# 780-00001_rev2_Pg3_SCH_Sinistro_ASP.net
KiCad netlist of a schematic drawn in Altium Designer
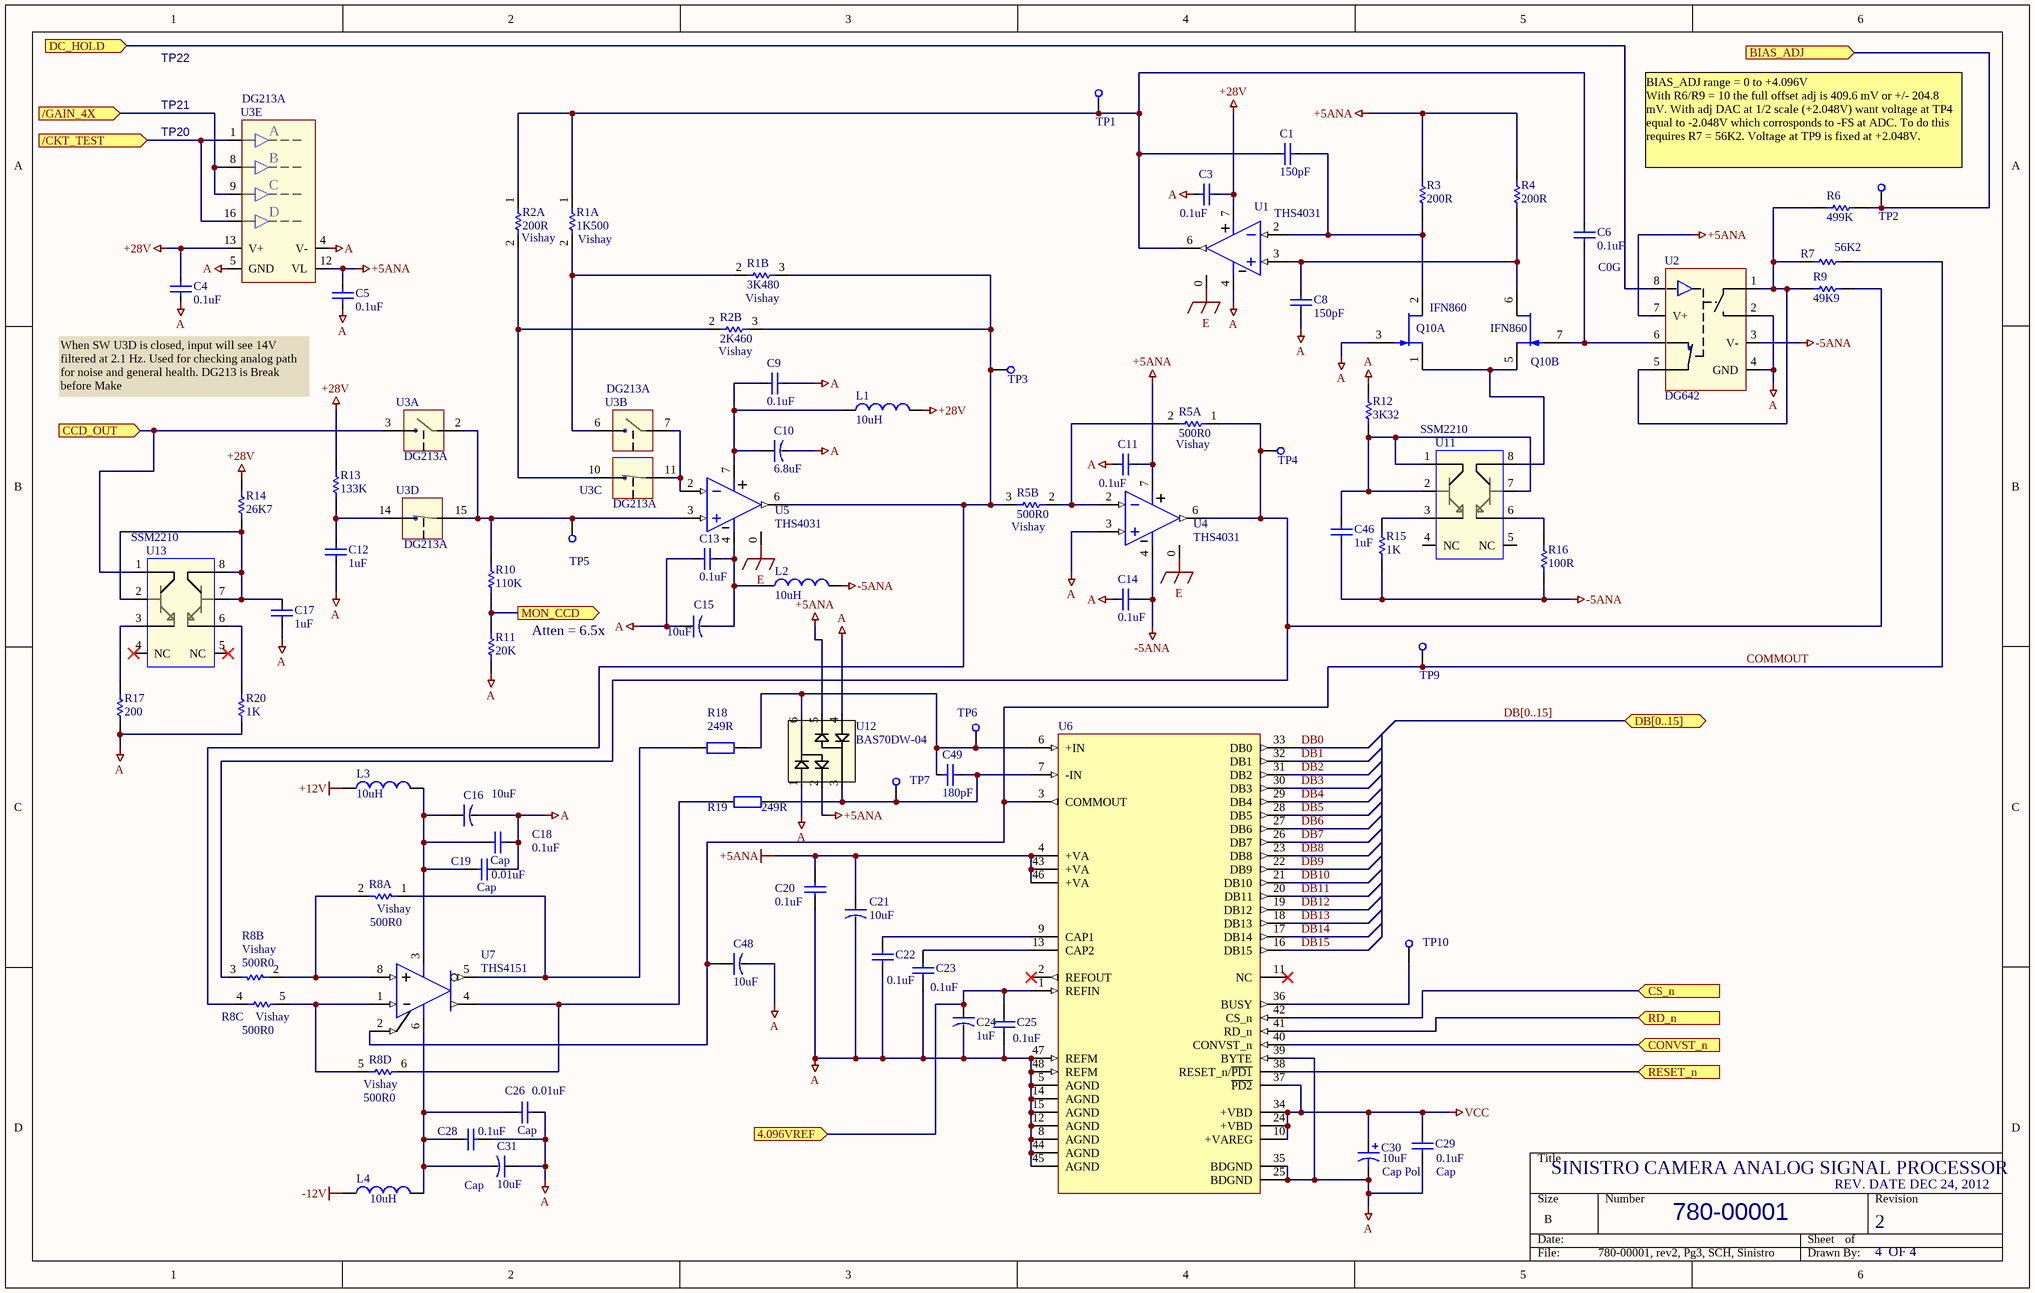
[diagram p0: 780-00001, rev2, Pg3, SCH, Sinistro ASP.SchDoc]

(export (version "E")
  (design (tool "Eeschema 10.0.6"))
  (components
    (comp (ref "C1")
      (value "150pF")
      (footprint "SMD_0805")
      (description "Capacitor")
      (fields (field (name "MANUFACTURER") "AVX") (field (name "Comment") "Cap SMD"))
      (libsource (lib "Richs Schematic Components") (part "Cap SMD"))
    )
    (comp (ref "C3")
      (value "0.1uF")
      (footprint "SMD_0805")
      (description "Capacitor")
      (fields (field (name "MANUFACTURER") "AVX") (field (name "Comment") "Cap"))
      (libsource (lib "Richs Schematic Components") (part "Cap SMD"))
    )
    (comp (ref "C4")
      (value "0.1uF")
      (footprint "SMD_0805")
      (description "Capacitor")
      (fields (field (name "MANUFACTURER") "AVX") (field (name "Comment") "Cap"))
      (libsource (lib "Richs Schematic Components") (part "Cap SMD"))
    )
    (comp (ref "C5")
      (value "0.1uF")
      (footprint "SMD_0805")
      (description "Capacitor")
      (fields (field (name "MANUFACTURER") "AVX") (field (name "Comment") "Cap"))
      (libsource (lib "Richs Schematic Components") (part "Cap SMD"))
    )
    (comp (ref "C6")
      (value "C0G")
      (footprint "1812")
      (description "Capacitor")
      (fields (field (name "ALTIUM_VALUE") "0.1uF") (field (name "MANUFACTURER") "TDK"))
      (libsource (lib "Richs Schematic Components") (part "Cap SMD"))
    )
    (comp (ref "C8")
      (value "150pF")
      (footprint "SMD_0805")
      (description "Capacitor")
      (fields (field (name "MANUFACTURER") "AVX") (field (name "Comment") "Cap SMD"))
      (libsource (lib "Richs Schematic Components") (part "Cap SMD"))
    )
    (comp (ref "C9")
      (value "0.1uF")
      (footprint "SMD_0805")
      (description "Capacitor")
      (fields (field (name "MANUFACTURER") "AVX") (field (name "Comment") "Cap"))
      (libsource (lib "Richs Schematic Components") (part "Cap SMD"))
    )
    (comp (ref "C10")
      (value "6.8uF")
      (footprint "SMD_CAP_6032")
      (description "outline 6.0mm x 3.2mm")
      (fields (field (name "MANUFACTURER") "Nichicon") (field (name "Comment") "35V"))
      (libsource (lib "Richs Schematic Components") (part "Cap Tant 35V"))
    )
    (comp (ref "C11")
      (value "0.1uF")
      (footprint "SMD_0805")
      (description "Capacitor")
      (fields (field (name "MANUFACTURER") "AVX") (field (name "Comment") "Cap"))
      (libsource (lib "Richs Schematic Components") (part "Cap SMD"))
    )
    (comp (ref "C12")
      (value "1uF")
      (footprint "SMD_0805")
      (description "Capacitor")
      (fields (field (name "MANUFACTURER") "MURATA") (field (name "Comment") "Cap SMD"))
      (libsource (lib "Richs Schematic Components") (part "Cap SMD"))
    )
    (comp (ref "C13")
      (value "0.1uF")
      (footprint "SMD_0805")
      (description "Capacitor")
      (fields (field (name "MANUFACTURER") "AVX") (field (name "Comment") "Cap"))
      (libsource (lib "Richs Schematic Components") (part "Cap SMD"))
    )
    (comp (ref "C14")
      (value "0.1uF")
      (footprint "SMD_0805")
      (description "Capacitor")
      (fields (field (name "MANUFACTURER") "AVX") (field (name "Comment") "Cap"))
      (libsource (lib "Richs Schematic Components") (part "Cap SMD"))
    )
    (comp (ref "C15")
      (value "10uF")
      (footprint "SMD_CAP_3216")
      (description "outline 3.2mm x 1.6mm")
      (fields (field (name "MANUFACTURER") "KEMET") (field (name "Comment") "Cap Pol"))
      (libsource (lib "Richs Schematic Components") (part "Cap Tant 15V"))
    )
    (comp (ref "C16")
      (value "10uF")
      (footprint "SMD_CAP_3216")
      (description "outline 3.2mm x 1.6mm")
      (fields (field (name "MANUFACTURER") "KEMET") (field (name "Comment") "Cap Pol"))
      (libsource (lib "Richs Schematic Components") (part "Cap Tant 15V"))
    )
    (comp (ref "C17")
      (value "1uF")
      (footprint "SMD_0805")
      (description "Capacitor")
      (fields (field (name "MANUFACTURER") "MURATA") (field (name "Comment") "Cap SMD"))
      (libsource (lib "Richs Schematic Components") (part "Cap SMD"))
    )
    (comp (ref "C18")
      (value "Cap")
      (footprint "SMD_0805")
      (description "Capacitor")
      (fields (field (name "ALTIUM_VALUE") "0.1uF") (field (name "MANUFACTURER") "AVX"))
      (libsource (lib "Miscellaneous Devices") (part "Cap"))
    )
    (comp (ref "C19")
      (value "Cap")
      (footprint "SMD_0805")
      (description "Capacitor")
      (fields (field (name "ALTIUM_VALUE") "0.01uF") (field (name "MANUFACTURER") "MURATA"))
      (libsource (lib "Miscellaneous Devices") (part "Cap"))
    )
    (comp (ref "C20")
      (value "0.1uF")
      (footprint "SMD_0805")
      (description "Capacitor")
      (fields (field (name "MANUFACTURER") "AVX") (field (name "Comment") "Cap"))
      (libsource (lib "Miscellaneous Devices") (part "Cap"))
    )
    (comp (ref "C21")
      (value "10uF")
      (footprint "SMD_CAP_3216")
      (description "outline 3.2mm x 1.6mm")
      (fields (field (name "MANUFACTURER") "KEMET") (field (name "Comment") "Cap Pol"))
      (libsource (lib "Richs Schematic Components") (part "Cap Tant 15V"))
    )
    (comp (ref "C22")
      (value "0.1uF")
      (footprint "SMD_0805")
      (description "Capacitor")
      (fields (field (name "MANUFACTURER") "AVX") (field (name "Comment") "Cap"))
      (libsource (lib "Miscellaneous Devices") (part "Cap"))
    )
    (comp (ref "C23")
      (value "0.1uF")
      (footprint "SMD_0805")
      (description "Capacitor")
      (fields (field (name "MANUFACTURER") "AVX") (field (name "Comment") "Cap"))
      (libsource (lib "Miscellaneous Devices") (part "Cap"))
    )
    (comp (ref "C24")
      (value "1uF")
      (footprint "SMD_CAP_3216")
      (description "outline 3.2mm x 1.6mm")
      (fields (field (name "MANUFACTURER") "MURATA") (field (name "Comment") "Cap Pol"))
      (libsource (lib "Richs Schematic Components") (part "Cap Tant 15V"))
    )
    (comp (ref "C25")
      (value "0.1uF")
      (footprint "SMD_0805")
      (description "Capacitor")
      (fields (field (name "MANUFACTURER") "AVX") (field (name "Comment") "Cap"))
      (libsource (lib "Miscellaneous Devices") (part "Cap"))
    )
    (comp (ref "C26")
      (value "Cap")
      (footprint "SMD_0805")
      (description "Capacitor")
      (fields (field (name "ALTIUM_VALUE") "0.01uF") (field (name "MANUFACTURER") "MURATA"))
      (libsource (lib "Miscellaneous Devices") (part "Cap"))
    )
    (comp (ref "C28")
      (value "Cap")
      (footprint "SMD_0805")
      (description "Capacitor")
      (fields (field (name "ALTIUM_VALUE") "0.1uF") (field (name "MANUFACTURER") "AVX"))
      (libsource (lib "Miscellaneous Devices") (part "Cap"))
    )
    (comp (ref "C29")
      (value "Cap")
      (footprint "SMD_0805")
      (description "Capacitor")
      (fields (field (name "ALTIUM_VALUE") "0.1uF") (field (name "MANUFACTURER") "AVX"))
      (libsource (lib "Miscellaneous Devices") (part "Cap"))
    )
    (comp (ref "C30")
      (value "Cap Pol")
      (footprint "SMD_CAP_3216")
      (fields (field (name "ALTIUM_VALUE") "10uF") (field (name "MANUFACTURER") "KEMET"))
      (libsource (lib "Miscellaneous Devices") (part "Cap Pol1"))
    )
    (comp (ref "C31")
      (value "10uF")
      (footprint "SMD_CAP_3216")
      (description "outline 3.2mm x 1.6mm")
      (fields (field (name "MANUFACTURER") "KEMET") (field (name "Comment") "Cap Pol"))
      (libsource (lib "") (part "Cap Tant 15V_1"))
    )
    (comp (ref "C46")
      (value "1uF")
      (footprint "SMD_0805")
      (description "Capacitor")
      (fields (field (name "MANUFACTURER") "MURATA") (field (name "Comment") "Cap"))
      (libsource (lib "Richs Schematic Components") (part "Cap SMD"))
    )
    (comp (ref "C48")
      (value "10uF")
      (footprint "SMD_CAP_3216")
      (description "outline 3.2mm x 1.6mm")
      (fields (field (name "MANUFACTURER") "KEMET") (field (name "Comment") "Cap Pol"))
      (libsource (lib "Richs Schematic Components") (part "Cap Tant 15V"))
    )
    (comp (ref "C49")
      (value "180pF")
      (footprint "SMD_0805")
      (description "Capacitor")
      (fields (field (name "MANUFACTURER") "AVX") (field (name "Comment") "Cap SMD"))
      (libsource (lib "Richs Schematic Components") (part "Cap SMD"))
    )
    (comp (ref "L1")
      (value "10uH")
      (footprint "SMD_1210_INDUCT")
      (description "Inductor")
      (fields (field (name "MANUFACTURER") "MURATA"))
      (libsource (lib "Richs Schematic Components") (part "Inductor"))
    )
    (comp (ref "L2")
      (value "10uH")
      (footprint "SMD_1210_INDUCT")
      (description "Inductor")
      (fields (field (name "MANUFACTURER") "MURATA"))
      (libsource (lib "Richs Schematic Components") (part "Inductor"))
    )
    (comp (ref "L3")
      (value "10uH")
      (footprint "SMD_1210_INDUCT")
      (description "Inductor")
      (fields (field (name "MANUFACTURER") "MURATA"))
      (libsource (lib "Miscellaneous Devices") (part "Inductor"))
    )
    (comp (ref "L4")
      (value "10uH")
      (footprint "SMD_1210_INDUCT")
      (description "Inductor")
      (fields (field (name "MANUFACTURER") "MURATA"))
      (libsource (lib "Miscellaneous Devices") (part "Inductor"))
    )
    (comp (ref "Q10")
      (value "IFN860")
      (footprint "TO-71")
      (description "N-JFET NJ450L Process")
      (fields (field (name "MANUFACTURER") "INTERFET"))
      (libsource (lib "Richs Schematic Components") (part "IFN860"))
    )
    (comp (ref "R1")
      (value "Vishay")
      (footprint "vishay 3 pin")
      (fields (field (name "ALTIUM_VALUE") "1K500"))
      (libsource (lib "Richs Schematic Components") (part "Res Match Pair"))
    )
    (comp (ref "R2")
      (value "Vishay")
      (footprint "vishay 3 pin")
      (fields (field (name "ALTIUM_VALUE") "2K460"))
      (libsource (lib "Richs Schematic Components") (part "Res Match Pair"))
    )
    (comp (ref "R3")
      (value "200R")
      (footprint "SMD_0805")
      (description "Resistor")
      (fields (field (name "MANUFACTURER") "Vishay") (field (name "Comment") "Res SMD"))
      (libsource (lib "Richs Schematic Components") (part "Res SMD"))
    )
    (comp (ref "R4")
      (value "200R")
      (footprint "SMD_0805")
      (description "Resistor")
      (fields (field (name "MANUFACTURER") "Vishay") (field (name "Comment") "Res SMD"))
      (libsource (lib "Richs Schematic Components") (part "Res SMD"))
    )
    (comp (ref "R5")
      (value "Vishay")
      (footprint "vishay 3 pin")
      (fields (field (name "ALTIUM_VALUE") "500R0"))
      (libsource (lib "Richs Schematic Components") (part "Res Match Pair"))
    )
    (comp (ref "R6")
      (value "499K")
      (footprint "SMD_0805")
      (description "Resistor")
      (fields (field (name "MANUFACTURER") "Vishay") (field (name "Comment") "Res SMD"))
      (libsource (lib "Richs Schematic Components") (part "Res SMD"))
    )
    (comp (ref "R7")
      (value "56K2")
      (footprint "SMD_0805")
      (description "Resistor")
      (fields (field (name "MANUFACTURER") "Vishay") (field (name "Comment") "Res SMD"))
      (libsource (lib "Richs Schematic Components") (part "Res SMD"))
    )
    (comp (ref "R8")
      (value "Vishay")
      (footprint "VISHAY 6 pin")
      (description "TCR matched")
      (fields (field (name "ALTIUM_VALUE") "500R0"))
      (libsource (lib "Richs Schematic Components") (part "Res Matched Quad"))
    )
    (comp (ref "R9")
      (value "49K9")
      (footprint "SMD_0805")
      (description "Resistor")
      (fields (field (name "MANUFACTURER") "Vishay") (field (name "Comment") "Res SMD"))
      (libsource (lib "Richs Schematic Components") (part "Res SMD"))
    )
    (comp (ref "R10")
      (value "110K")
      (footprint "SMD_0805")
      (description "Resistor")
      (fields (field (name "MANUFACTURER") "Vishay") (field (name "Comment") "Res SMD"))
      (libsource (lib "Richs Schematic Components") (part "Res SMD"))
    )
    (comp (ref "R11")
      (value "20K")
      (footprint "SMD_0805")
      (description "Resistor")
      (fields (field (name "MANUFACTURER") "Vishay") (field (name "Comment") "Res SMD"))
      (libsource (lib "Richs Schematic Components") (part "Res SMD"))
    )
    (comp (ref "R12")
      (value "3K32")
      (footprint "SMD_0805")
      (description "Resistor")
      (fields (field (name "MANUFACTURER") "Vishay") (field (name "Comment") "Res SMD"))
      (libsource (lib "Richs Schematic Components") (part "Res SMD"))
    )
    (comp (ref "R13")
      (value "133K")
      (footprint "SMD_0805")
      (description "Resistor")
      (fields (field (name "MANUFACTURER") "Vishay") (field (name "Comment") "Res SMD"))
      (libsource (lib "Richs Schematic Components") (part "Res SMD"))
    )
    (comp (ref "R14")
      (value "26K7")
      (footprint "SMD_0805")
      (description "Resistor")
      (fields (field (name "MANUFACTURER") "Vishay") (field (name "Comment") "Res SMD"))
      (libsource (lib "Richs Schematic Components") (part "Res SMD"))
    )
    (comp (ref "R15")
      (value "1K")
      (footprint "SMD_0805")
      (description "Resistor")
      (fields (field (name "MANUFACTURER") "Vishay") (field (name "Comment") "Res SMD"))
      (libsource (lib "Richs Schematic Components") (part "Res SMD"))
    )
    (comp (ref "R16")
      (value "100R")
      (footprint "SMD_0805")
      (description "Resistor")
      (fields (field (name "MANUFACTURER") "Vishay") (field (name "Comment") "Res SMD"))
      (libsource (lib "Richs Schematic Components") (part "Res SMD"))
    )
    (comp (ref "R17")
      (value "200")
      (footprint "SMD_0805")
      (description "Resistor")
      (fields (field (name "MANUFACTURER") "Vishay") (field (name "Comment") "Res SMD"))
      (libsource (lib "Richs Schematic Components") (part "Res SMD"))
    )
    (comp (ref "R18")
      (value "249R")
      (footprint "SMD_0805")
      (description "Resistor")
      (fields (field (name "MANUFACTURER") "Vishay") (field (name "Comment") "Res SMD"))
      (libsource (lib "Miscellaneous Devices") (part "Res2"))
    )
    (comp (ref "R19")
      (value "249R")
      (footprint "SMD_0805")
      (description "Resistor")
      (fields (field (name "MANUFACTURER") "Vishay") (field (name "Comment") "Res SMD"))
      (libsource (lib "Miscellaneous Devices") (part "Res2"))
    )
    (comp (ref "R20")
      (value "1K")
      (footprint "SMD_0805")
      (description "Resistor")
      (fields (field (name "MANUFACTURER") "Vishay") (field (name "Comment") "Res SMD"))
      (libsource (lib "Richs Schematic Components") (part "Res SMD"))
    )
    (comp (ref "TP1")
      (value "Test point")
      (footprint "Protel 99SE BANKS PCB:PAD_80D_052H")
      (description "Test Point")
      (fields (field (name "MANUFACTURER") "Keystone"))
      (libsource (lib "Richs Schematic Components") (part "Test point"))
    )
    (comp (ref "TP2")
      (value "Test point")
      (footprint "Protel 99SE BANKS PCB:PAD_80D_052H")
      (description "Test Point")
      (fields (field (name "MANUFACTURER") "Keystone"))
      (libsource (lib "Richs Schematic Components") (part "Test point"))
    )
    (comp (ref "TP3")
      (value "Test point")
      (footprint "Protel 99SE BANKS PCB:PAD_80D_052H")
      (description "Test Point")
      (fields (field (name "MANUFACTURER") "Keystone"))
      (libsource (lib "Richs Schematic Components") (part "Test point"))
    )
    (comp (ref "TP4")
      (value "Test point")
      (footprint "Protel 99SE BANKS PCB:PAD_80D_052H")
      (description "Test Point")
      (fields (field (name "MANUFACTURER") "Keystone"))
      (libsource (lib "Richs Schematic Components") (part "Test point"))
    )
    (comp (ref "TP5")
      (value "Test point")
      (footprint "Protel 99SE BANKS PCB:PAD_80D_052H")
      (description "Test Point")
      (fields (field (name "MANUFACTURER") "Keystone"))
      (libsource (lib "Richs Schematic Components") (part "Test point"))
    )
    (comp (ref "TP6")
      (value "Test point")
      (footprint "Protel 99SE BANKS PCB:PAD_80D_052H")
      (description "Test Point")
      (fields (field (name "MANUFACTURER") "Keystone"))
      (libsource (lib "Richs Schematic Components") (part "Test point"))
    )
    (comp (ref "TP7")
      (value "Test point")
      (footprint "Protel 99SE BANKS PCB:PAD_80D_052H")
      (description "Test Point")
      (fields (field (name "MANUFACTURER") "Keystone"))
      (libsource (lib "Richs Schematic Components") (part "Test point"))
    )
    (comp (ref "TP9")
      (value "Test point")
      (footprint "Protel 99SE BANKS PCB:PAD_80D_052H")
      (description "Test Point")
      (fields (field (name "MANUFACTURER") "Keystone"))
      (libsource (lib "Richs Schematic Components") (part "Test point"))
    )
    (comp (ref "TP10")
      (value "Test point")
      (footprint "Protel 99SE BANKS PCB:PAD_80D_052H")
      (description "Test Point")
      (fields (field (name "MANUFACTURER") "Keystone"))
      (libsource (lib "Richs Schematic Components") (part "Test point"))
    )
    (comp (ref "U1")
      (value "THS4031")
      (footprint "MSOP with PowerPAD")
      (description "Low Noise, High Speed Amplifier")
      (fields (field (name "MANUFACTURER") "TEXAS INST"))
      (libsource (lib "Richs Schematic Components") (part "THS4031"))
    )
    (comp (ref "U2")
      (value "DG642")
      (footprint "Burr-Brown Footprints:182H_M")
      (fields (field (name "MANUFACTURER") "VISHAY"))
      (libsource (lib "Richs Schematic Components") (part "DG642"))
    )
    (comp (ref "U3")
      (value "DG213A")
      (footprint "Miscellaneous Devices:SOIC16")
      (description "DG213 QUAD NO/NC")
      (fields (field (name "MANUFACTURER") "VISHAY"))
      (libsource (lib "Richs Schematic Components") (part "DG213A"))
    )
    (comp (ref "U4")
      (value "THS4031")
      (footprint "MSOP with PowerPAD")
      (description "Low Noise, High Speed Amplifier")
      (fields (field (name "MANUFACTURER") "TEXAS INST"))
      (libsource (lib "Richs Schematic Components") (part "THS4031"))
    )
    (comp (ref "U5")
      (value "THS4031")
      (footprint "MSOP with PowerPAD")
      (description "Low Noise, High Speed Amplifier")
      (fields (field (name "MANUFACTURER") "TEXAS INST"))
      (libsource (lib "Richs Schematic Components") (part "THS4031"))
    )
    (comp (ref "U6")
      (value "0.2 ppm")
      (footprint "Lattice Semiconductor Footprints:TQFP48_m")
      (description "AD8422")
      (fields (field (name "MANUFACTURER") "TEXAS INST"))
      (libsource (lib "Richs Schematic Components") (part "ADS8422"))
    )
    (comp (ref "U7")
      (value "THS4151")
      (footprint "Burr-Brown Footprints:182H_M")
      (description "DIFF AMP")
      (fields (field (name "MANUFACTURER") "TEXAS INST"))
      (libsource (lib "Richs Schematic Components") (part "THS4151"))
    )
    (comp (ref "U11")
      (value "SSM2210")
      (footprint "SO-8_M")
      (description "Dual Matched NPN")
      (fields (field (name "MANUFACTURER") "ANALOG DEVICES"))
      (libsource (lib "Richs Schematic Components") (part "SSM2210"))
    )
    (comp (ref "U12")
      (value "BAS70DW-04")
      (footprint "SOT-363")
      (description "Dual series array")
      (fields (field (name "MANUFACTURER") "DIODES INC") (field (name "Comment") "Diode array"))
      (libsource (lib "Richs Schematic Components") (part "Diode array"))
    )
    (comp (ref "U13")
      (value "SSM2210")
      (footprint "SO-8_M")
      (description "Dual Matched NPN")
      (fields (field (name "MANUFACTURER") "ANALOG DEVICES"))
      (libsource (lib "Richs Schematic Components") (part "SSM2210"))
    )
  )
  (nets
    (net (code "1") (name "+5ANA") (class "Default")
      (node (ref "C11") (pin "2") (pinfunction "2_2") (pintype "passive"))
      (node (ref "C20") (pin "2") (pinfunction "2_2") (pintype "passive"))
      (node (ref "C21") (pin "1") (pinfunction "1_1") (pintype "passive"))
      (node (ref "C5") (pin "2") (pinfunction "2_2") (pintype "passive"))
      (node (ref "R3") (pin "1") (pinfunction "1_1") (pintype "passive"))
      (node (ref "R4") (pin "1") (pinfunction "1_1") (pintype "passive"))
      (node (ref "U12") (pin "2") (pinfunction "C1_2") (pintype "passive"))
      (node (ref "U12") (pin "5") (pinfunction "C2_5") (pintype "passive"))
      (node (ref "U2") (pin "7") (pinfunction "V+_7") (pintype "passive"))
      (node (ref "U3") (pin "12") (pinfunction "VL_12") (pintype "passive"))
      (node (ref "U4") (pin "7") (pinfunction "V+_7") (pintype "power_in"))
      (node (ref "U6") (pin "4") (pinfunction "+VA_4") (pintype "passive"))
      (node (ref "U6") (pin "43") (pinfunction "+VA_43") (pintype "passive"))
      (node (ref "U6") (pin "46") (pinfunction "+VA_46") (pintype "passive"))
    )
    (net (code "2") (name "+12V") (class "Default")
      (node (ref "L3") (pin "1") (pinfunction "1_1") (pintype "passive"))
    )
    (net (code "3") (name "+28V") (class "Default")
      (node (ref "C3") (pin "2") (pinfunction "2_2") (pintype "passive"))
      (node (ref "C4") (pin "2") (pinfunction "2_2") (pintype "passive"))
      (node (ref "L1") (pin "2") (pinfunction "2_2") (pintype "passive"))
      (node (ref "R13") (pin "2") (pinfunction "2_2") (pintype "passive"))
      (node (ref "R14") (pin "2") (pinfunction "2_2") (pintype "passive"))
      (node (ref "U1") (pin "7") (pinfunction "V+_7") (pintype "power_in"))
      (node (ref "U3") (pin "13") (pinfunction "V+_13") (pintype "passive"))
    )
    (net (code "4") (name "-5ANA") (class "Default")
      (node (ref "C14") (pin "2") (pinfunction "2_2") (pintype "passive"))
      (node (ref "C46") (pin "1") (pinfunction "1_1") (pintype "passive"))
      (node (ref "L2") (pin "2") (pinfunction "2_2") (pintype "passive"))
      (node (ref "R15") (pin "2") (pinfunction "2_2") (pintype "passive"))
      (node (ref "R16") (pin "2") (pinfunction "2_2") (pintype "passive"))
      (node (ref "U2") (pin "3") (pinfunction "V-_3") (pintype "passive"))
      (node (ref "U4") (pin "4") (pinfunction "V-_4") (pintype "power_in"))
    )
    (net (code "5") (name "-12V") (class "Default")
      (node (ref "L4") (pin "1") (pinfunction "1_1") (pintype "passive"))
    )
    (net (code "6") (name "/4.096VREF") (class "Default")
      (node (ref "C24") (pin "1") (pinfunction "1_1") (pintype "passive"))
      (node (ref "C25") (pin "2") (pinfunction "2_2") (pintype "passive"))
      (node (ref "U6") (pin "1") (pinfunction "REFIN_1") (pintype "input"))
    )
    (net (code "7") (name "/BIAS_ADJ") (class "Default")
      (node (ref "R6") (pin "2") (pinfunction "2_2") (pintype "passive"))
      (node (ref "TP2") (pin "1") (pinfunction "TP_1") (pintype "passive"))
    )
    (net (code "8") (name "/CCD_OUT") (class "Default")
      (node (ref "U13") (pin "1") (pinfunction "C1_1") (pintype "passive"))
      (node (ref "U3") (pin "3") (pinfunction "S1_3") (pintype "passive"))
    )
    (net (code "9") (name "/COMMOUT") (class "Default")
      (node (ref "C48") (pin "1") (pinfunction "1_1") (pintype "passive"))
      (node (ref "R7") (pin "2") (pinfunction "2_2") (pintype "passive"))
      (node (ref "TP9") (pin "1") (pinfunction "TP_1") (pintype "passive"))
      (node (ref "U6") (pin "3") (pinfunction "COMMOUT_3") (pintype "output"))
      (node (ref "U7") (pin "2") (pinfunction "VOCM_2") (pintype "input"))
    )
    (net (code "10") (name "/CONVST_n") (class "Default")
      (node (ref "U6") (pin "40") (pinfunction "CONVST_n_40") (pintype "input"))
    )
    (net (code "11") (name "/CS_n") (class "Default")
      (node (ref "U6") (pin "42") (pinfunction "CS_n_42") (pintype "input"))
    )
    (net (code "12") (name "/DB0") (class "Default")
      (node (ref "U6") (pin "33") (pinfunction "DB0_33") (pintype "output"))
    )
    (net (code "13") (name "/DB1") (class "Default")
      (node (ref "U6") (pin "32") (pinfunction "DB1_32") (pintype "output"))
    )
    (net (code "14") (name "/DB2") (class "Default")
      (node (ref "U6") (pin "31") (pinfunction "DB2_31") (pintype "output"))
    )
    (net (code "15") (name "/DB3") (class "Default")
      (node (ref "U6") (pin "30") (pinfunction "DB3_30") (pintype "output"))
    )
    (net (code "16") (name "/DB4") (class "Default")
      (node (ref "U6") (pin "29") (pinfunction "DB4_29") (pintype "output"))
    )
    (net (code "17") (name "/DB5") (class "Default")
      (node (ref "U6") (pin "28") (pinfunction "DB5_28") (pintype "output"))
    )
    (net (code "18") (name "/DB6") (class "Default")
      (node (ref "U6") (pin "27") (pinfunction "DB6_27") (pintype "output"))
    )
    (net (code "19") (name "/DB7") (class "Default")
      (node (ref "U6") (pin "26") (pinfunction "DB7_26") (pintype "output"))
    )
    (net (code "20") (name "/DB8") (class "Default")
      (node (ref "U6") (pin "23") (pinfunction "DB8_23") (pintype "output"))
    )
    (net (code "21") (name "/DB9") (class "Default")
      (node (ref "U6") (pin "22") (pinfunction "DB9_22") (pintype "output"))
    )
    (net (code "22") (name "/DB10") (class "Default")
      (node (ref "U6") (pin "21") (pinfunction "DB10_21") (pintype "output"))
    )
    (net (code "23") (name "/DB11") (class "Default")
      (node (ref "U6") (pin "20") (pinfunction "DB11_20") (pintype "output"))
    )
    (net (code "24") (name "/DB12") (class "Default")
      (node (ref "U6") (pin "19") (pinfunction "DB12_19") (pintype "output"))
    )
    (net (code "25") (name "/DB13") (class "Default")
      (node (ref "U6") (pin "18") (pinfunction "DB13_18") (pintype "output"))
    )
    (net (code "26") (name "/DB14") (class "Default")
      (node (ref "U6") (pin "17") (pinfunction "DB14_17") (pintype "output"))
    )
    (net (code "27") (name "/DB15") (class "Default")
      (node (ref "U6") (pin "16") (pinfunction "DB15_16") (pintype "output"))
    )
    (net (code "29") (name "/DC_HOLD") (class "Default")
      (node (ref "U2") (pin "8") (pinfunction "IN_8") (pintype "passive"))
    )
    (net (code "30") (name "/MON_CCD") (class "Default")
      (node (ref "R10") (pin "1") (pinfunction "1_1") (pintype "passive"))
      (node (ref "R11") (pin "2") (pinfunction "2_2") (pintype "passive"))
    )
    (net (code "31") (name "/RD_n") (class "Default")
      (node (ref "U6") (pin "41") (pinfunction "RD_n_41") (pintype "input"))
    )
    (net (code "32") (name "/RESET_n") (class "Default")
      (node (ref "U6") (pin "38") (pinfunction "RESET_n/~{PD1}_38") (pintype "passive"))
    )
    (net (code "33") (name "/{slash}CKT_TEST") (class "Default")
      (node (ref "U3") (pin "1") (pinfunction "IN1_1") (pintype "passive"))
      (node (ref "U3") (pin "16") (pinfunction "IN1_16") (pintype "passive"))
    )
    (net (code "34") (name "/{slash}GAIN_4X") (class "Default")
      (node (ref "U3") (pin "8") (pinfunction "IN1_8") (pintype "passive"))
      (node (ref "U3") (pin "9") (pinfunction "IN1_9") (pintype "passive"))
    )
    (net (code "35") (name "A") (class "Default")
      (node (ref "C10") (pin "neg") (pinfunction "2_neg") (pintype "passive"))
      (node (ref "C11") (pin "1") (pinfunction "1_1") (pintype "passive"))
      (node (ref "C12") (pin "1") (pinfunction "1_1") (pintype "passive"))
      (node (ref "C13") (pin "1") (pinfunction "1_1") (pintype "passive"))
      (node (ref "C14") (pin "1") (pinfunction "1_1") (pintype "passive"))
      (node (ref "C15") (pin "1") (pinfunction "1_1") (pintype "passive"))
      (node (ref "C16") (pin "2") (pinfunction "2_2") (pintype "passive"))
      (node (ref "C17") (pin "1") (pinfunction "1_1") (pintype "passive"))
      (node (ref "C18") (pin "2") (pinfunction "2_2") (pintype "passive"))
      (node (ref "C19") (pin "2") (pinfunction "2_2") (pintype "passive"))
      (node (ref "C20") (pin "1") (pinfunction "1_1") (pintype "passive"))
      (node (ref "C21") (pin "2") (pinfunction "2_2") (pintype "passive"))
      (node (ref "C22") (pin "1") (pinfunction "1_1") (pintype "passive"))
      (node (ref "C23") (pin "1") (pinfunction "1_1") (pintype "passive"))
      (node (ref "C24") (pin "2") (pinfunction "2_2") (pintype "passive"))
      (node (ref "C25") (pin "1") (pinfunction "1_1") (pintype "passive"))
      (node (ref "C26") (pin "2") (pinfunction "2_2") (pintype "passive"))
      (node (ref "C28") (pin "2") (pinfunction "2_2") (pintype "passive"))
      (node (ref "C29") (pin "1") (pinfunction "1_1") (pintype "passive"))
      (node (ref "C3") (pin "1") (pinfunction "1_1") (pintype "passive"))
      (node (ref "C30") (pin "2") (pinfunction "2_2") (pintype "passive"))
      (node (ref "C31") (pin "1") (pinfunction "1_1") (pintype "passive"))
      (node (ref "C4") (pin "1") (pinfunction "1_1") (pintype "passive"))
      (node (ref "C48") (pin "2") (pinfunction "2_2") (pintype "passive"))
      (node (ref "C5") (pin "1") (pinfunction "1_1") (pintype "passive"))
      (node (ref "C8") (pin "1") (pinfunction "1_1") (pintype "passive"))
      (node (ref "C9") (pin "2") (pinfunction "2_2") (pintype "passive"))
      (node (ref "Q10") (pin "3") (pinfunction "G_3") (pintype "passive"))
      (node (ref "R11") (pin "1") (pinfunction "1_1") (pintype "passive"))
      (node (ref "R12") (pin "1") (pinfunction "1_1") (pintype "passive"))
      (node (ref "R17") (pin "1") (pinfunction "1_1") (pintype "passive"))
      (node (ref "R20") (pin "1") (pinfunction "1_1") (pintype "passive"))
      (node (ref "U1") (pin "4") (pinfunction "V-_4") (pintype "power_in"))
      (node (ref "U12") (pin "1") (pinfunction "A1_1") (pintype "passive"))
      (node (ref "U12") (pin "4") (pinfunction "A2_4") (pintype "passive"))
      (node (ref "U2") (pin "2") (pinfunction "D1_2") (pintype "passive"))
      (node (ref "U2") (pin "4") (pinfunction "GND_4") (pintype "passive"))
      (node (ref "U3") (pin "4") (pinfunction "V-_4") (pintype "passive"))
      (node (ref "U3") (pin "5") (pinfunction "GND_5") (pintype "passive"))
      (node (ref "U4") (pin "3") (pinfunction "IN+_3") (pintype "input"))
      (node (ref "U6") (pin "12") (pinfunction "AGND_12") (pintype "passive"))
      (node (ref "U6") (pin "14") (pinfunction "AGND_14") (pintype "passive"))
      (node (ref "U6") (pin "15") (pinfunction "AGND_15") (pintype "passive"))
      (node (ref "U6") (pin "25") (pinfunction "BDGND_25") (pintype "passive"))
      (node (ref "U6") (pin "35") (pinfunction "BDGND_35") (pintype "passive"))
      (node (ref "U6") (pin "39") (pinfunction "BYTE_39") (pintype "input"))
      (node (ref "U6") (pin "44") (pinfunction "AGND_44") (pintype "passive"))
      (node (ref "U6") (pin "45") (pinfunction "AGND_45") (pintype "passive"))
      (node (ref "U6") (pin "47") (pinfunction "REFM_47") (pintype "input"))
      (node (ref "U6") (pin "48") (pinfunction "REFM_48") (pintype "input"))
      (node (ref "U6") (pin "5") (pinfunction "AGND_5") (pintype "passive"))
      (node (ref "U6") (pin "8") (pinfunction "AGND_8") (pintype "passive"))
    )
    (net (code "36") (name "E") (class "Default")
      (node (ref "U1") (pin "0") (pinfunction "PowerPAD_0") (pintype "passive"))
      (node (ref "U4") (pin "0") (pinfunction "PowerPAD_0") (pintype "passive"))
      (node (ref "U5") (pin "0") (pinfunction "PowerPAD_0") (pintype "passive"))
    )
    (net (code "37") (name "Net-(C10-1)") (class "Default")
      (node (ref "C10") (pin "pos") (pinfunction "1_pos") (pintype "passive"))
      (node (ref "C9") (pin "1") (pinfunction "1_1") (pintype "passive"))
      (node (ref "L1") (pin "1") (pinfunction "1_1") (pintype "passive"))
      (node (ref "U5") (pin "7") (pinfunction "V+_7") (pintype "power_in"))
    )
    (net (code "38") (name "Net-(Q10A-D)") (class "Default")
      (node (ref "C1") (pin "2") (pinfunction "2_2") (pintype "passive"))
      (node (ref "Q10") (pin "2") (pinfunction "D_2") (pintype "passive"))
      (node (ref "R3") (pin "2") (pinfunction "2_2") (pintype "passive"))
      (node (ref "U1") (pin "2") (pinfunction "IN-_2") (pintype "input"))
    )
    (net (code "39") (name "Net-(Q10A-S)") (class "Default")
      (node (ref "Q10") (pin "1") (pinfunction "S_1") (pintype "passive"))
      (node (ref "Q10") (pin "5") (pinfunction "S_5") (pintype "passive"))
      (node (ref "U11") (pin "8") (pinfunction "C2_8") (pintype "passive"))
    )
    (net (code "40") (name "Net-(Q10B-D)") (class "Default")
      (node (ref "C8") (pin "2") (pinfunction "2_2") (pintype "passive"))
      (node (ref "Q10") (pin "6") (pinfunction "D_6") (pintype "passive"))
      (node (ref "R4") (pin "2") (pinfunction "2_2") (pintype "passive"))
      (node (ref "U1") (pin "3") (pinfunction "IN+_3") (pintype "input"))
    )
    (net (code "41") (name "Net-(Q10B-G)") (class "Default")
      (node (ref "C6") (pin "1") (pinfunction "1_1") (pintype "passive"))
      (node (ref "Q10") (pin "7") (pinfunction "G_7") (pintype "passive"))
      (node (ref "U2") (pin "6") (pinfunction "D2_6") (pintype "passive"))
    )
    (net (code "42") (name "Net-(TP1-TP)") (class "Default")
      (node (ref "C1") (pin "1") (pinfunction "1_1") (pintype "passive"))
      (node (ref "C6") (pin "2") (pinfunction "2_2") (pintype "passive"))
      (node (ref "R1") (pin "1") (pinfunction "1_1") (pintype "passive"))
      (node (ref "R2") (pin "1") (pinfunction "1_1") (pintype "passive"))
      (node (ref "TP1") (pin "1") (pinfunction "TP_1") (pintype "passive"))
      (node (ref "U1") (pin "6") (pinfunction "OUT_6") (pintype "output"))
    )
    (net (code "43") (name "Net-(TP3-TP)") (class "Default")
      (node (ref "R1") (pin "3") (pinfunction "3_3") (pintype "passive"))
      (node (ref "R2") (pin "3") (pinfunction "3_3") (pintype "passive"))
      (node (ref "R5") (pin "3") (pinfunction "3_3") (pintype "passive"))
      (node (ref "R8") (pin "4") (pinfunction "4_4") (pintype "passive"))
      (node (ref "TP3") (pin "1") (pinfunction "TP_1") (pintype "passive"))
      (node (ref "U5") (pin "6") (pinfunction "OUT_6") (pintype "output"))
    )
    (net (code "44") (name "Net-(TP4-TP)") (class "Default")
      (node (ref "R5") (pin "1") (pinfunction "1_1") (pintype "passive"))
      (node (ref "R8") (pin "3") (pinfunction "3_3") (pintype "passive"))
      (node (ref "R9") (pin "2") (pinfunction "2_2") (pintype "passive"))
      (node (ref "TP4") (pin "1") (pinfunction "TP_1") (pintype "passive"))
      (node (ref "U4") (pin "6") (pinfunction "OUT_6") (pintype "output"))
    )
    (net (code "45") (name "Net-(TP5-TP)") (class "Default")
      (node (ref "R10") (pin "2") (pinfunction "2_2") (pintype "passive"))
      (node (ref "TP5") (pin "1") (pinfunction "TP_1") (pintype "passive"))
      (node (ref "U3") (pin "15") (pinfunction "D4_15") (pintype "passive"))
      (node (ref "U3") (pin "2") (pinfunction "D1_2") (pintype "passive"))
      (node (ref "U5") (pin "3") (pinfunction "IN+_3") (pintype "input"))
    )
    (net (code "46") (name "Net-(TP6-TP)") (class "Default")
      (node (ref "C49") (pin "1") (pinfunction "1_1") (pintype "passive"))
      (node (ref "R18") (pin "2") (pinfunction "2_2") (pintype "passive"))
      (node (ref "TP6") (pin "1") (pinfunction "TP_1") (pintype "passive"))
      (node (ref "U12") (pin "6") (pinfunction "AC1_6") (pintype "passive"))
      (node (ref "U6") (pin "6") (pinfunction "+IN_6") (pintype "input"))
    )
    (net (code "47") (name "Net-(TP7-TP)") (class "Default")
      (node (ref "C49") (pin "2") (pinfunction "2_2") (pintype "passive"))
      (node (ref "R19") (pin "2") (pinfunction "2_2") (pintype "passive"))
      (node (ref "TP7") (pin "1") (pinfunction "TP_1") (pintype "passive"))
      (node (ref "U12") (pin "3") (pinfunction "AC2_3") (pintype "passive"))
      (node (ref "U6") (pin "7") (pinfunction "-IN_7") (pintype "input"))
    )
    (net (code "48") (name "Net-(TP10-TP)") (class "Default")
      (node (ref "TP10") (pin "1") (pinfunction "TP_1") (pintype "passive"))
      (node (ref "U6") (pin "36") (pinfunction "BUSY_36") (pintype "output"))
    )
    (net (code "49") (name "Net-(U2-S1)") (class "Default")
      (node (ref "R6") (pin "1") (pinfunction "1_1") (pintype "passive"))
      (node (ref "R7") (pin "1") (pinfunction "1_1") (pintype "passive"))
      (node (ref "R9") (pin "1") (pinfunction "1_1") (pintype "passive"))
      (node (ref "U2") (pin "1") (pinfunction "S1_1") (pintype "passive"))
      (node (ref "U2") (pin "5") (pinfunction "S2_5") (pintype "passive"))
    )
    (net (code "50") (name "Net-(U3B-D2)") (class "Default")
      (node (ref "R1") (pin "2") (pinfunction "2_2") (pintype "passive"))
      (node (ref "U3") (pin "6") (pinfunction "D2_6") (pintype "passive"))
    )
    (net (code "51") (name "Net-(U3B-S2)") (class "Default")
      (node (ref "U3") (pin "11") (pinfunction "D3_11") (pintype "passive"))
      (node (ref "U3") (pin "7") (pinfunction "S2_7") (pintype "passive"))
      (node (ref "U5") (pin "2") (pinfunction "IN-_2") (pintype "input"))
    )
    (net (code "52") (name "Net-(U3C-S3)") (class "Default")
      (node (ref "R2") (pin "2") (pinfunction "2_2") (pintype "passive"))
      (node (ref "U3") (pin "10") (pinfunction "S3_10") (pintype "passive"))
    )
    (net (code "53") (name "Net-(U3D-S4)") (class "Default")
      (node (ref "C12") (pin "2") (pinfunction "2_2") (pintype "passive"))
      (node (ref "R13") (pin "1") (pinfunction "1_1") (pintype "passive"))
      (node (ref "U3") (pin "14") (pinfunction "S4_14") (pintype "passive"))
    )
    (net (code "54") (name "Net-(U4-IN-)") (class "Default")
      (node (ref "R5") (pin "2") (pinfunction "2_2") (pintype "passive"))
      (node (ref "U4") (pin "2") (pinfunction "IN-_2") (pintype "input"))
    )
    (net (code "55") (name "Net-(U5-V-)") (class "Default")
      (node (ref "C13") (pin "2") (pinfunction "2_2") (pintype "passive"))
      (node (ref "C15") (pin "2") (pinfunction "2_2") (pintype "passive"))
      (node (ref "L2") (pin "1") (pinfunction "1_1") (pintype "passive"))
      (node (ref "U5") (pin "4") (pinfunction "V-_4") (pintype "power_in"))
    )
    (net (code "56") (name "Net-(U6-CAP1)") (class "Default")
      (node (ref "C22") (pin "2") (pinfunction "2_2") (pintype "passive"))
      (node (ref "U6") (pin "9") (pinfunction "CAP1_9") (pintype "passive"))
    )
    (net (code "57") (name "Net-(U6-CAP2)") (class "Default")
      (node (ref "C23") (pin "2") (pinfunction "2_2") (pintype "passive"))
      (node (ref "U6") (pin "13") (pinfunction "CAP2_13") (pintype "passive"))
    )
    (net (code "58") (name "Net-(U7-+IN)") (class "Default")
      (node (ref "R8") (pin "2") (pinfunction "2_2") (pintype "passive"))
      (node (ref "U7") (pin "8") (pinfunction "+IN_8") (pintype "input"))
    )
    (net (code "59") (name "Net-(U7-+OUT)") (class "Default")
      (node (ref "R19") (pin "1") (pinfunction "1_1") (pintype "passive"))
      (node (ref "R8") (pin "6") (pinfunction "6_6") (pintype "passive"))
      (node (ref "U7") (pin "4") (pinfunction "+OUT_4") (pintype "output"))
    )
    (net (code "60") (name "Net-(U7--IN)") (class "Default")
      (node (ref "R8") (pin "5") (pinfunction "5_5") (pintype "passive"))
      (node (ref "U7") (pin "1") (pinfunction "-IN_1") (pintype "input"))
    )
    (net (code "61") (name "Net-(U7--OUT)") (class "Default")
      (node (ref "R18") (pin "1") (pinfunction "1_1") (pintype "passive"))
      (node (ref "R8") (pin "1") (pinfunction "1_1") (pintype "passive"))
      (node (ref "U7") (pin "5") (pinfunction "-OUT_5") (pintype "output"))
    )
    (net (code "62") (name "Net-(U7-V+)") (class "Default")
      (node (ref "C16") (pin "1") (pinfunction "1_1") (pintype "passive"))
      (node (ref "C18") (pin "1") (pinfunction "1_1") (pintype "passive"))
      (node (ref "C19") (pin "1") (pinfunction "1_1") (pintype "passive"))
      (node (ref "L3") (pin "2") (pinfunction "2_2") (pintype "passive"))
      (node (ref "U7") (pin "3") (pinfunction "V+_3") (pintype "passive"))
    )
    (net (code "63") (name "Net-(U7-V-)") (class "Default")
      (node (ref "C26") (pin "1") (pinfunction "1_1") (pintype "passive"))
      (node (ref "C28") (pin "1") (pinfunction "1_1") (pintype "passive"))
      (node (ref "C31") (pin "2") (pinfunction "2_2") (pintype "passive"))
      (node (ref "L4") (pin "2") (pinfunction "2_2") (pintype "passive"))
      (node (ref "U7") (pin "6") (pinfunction "V-_6") (pintype "passive"))
    )
    (net (code "64") (name "Net-(U11-B1)") (class "Default")
      (node (ref "C46") (pin "2") (pinfunction "2_2") (pintype "passive"))
      (node (ref "R12") (pin "2") (pinfunction "2_2") (pintype "passive"))
      (node (ref "U11") (pin "1") (pinfunction "C1_1") (pintype "passive"))
      (node (ref "U11") (pin "2") (pinfunction "B1_2") (pintype "passive"))
      (node (ref "U11") (pin "7") (pinfunction "B2_7") (pintype "passive"))
    )
    (net (code "65") (name "Net-(U11-E1)") (class "Default")
      (node (ref "R15") (pin "1") (pinfunction "1_1") (pintype "passive"))
      (node (ref "U11") (pin "3") (pinfunction "E1_3") (pintype "passive"))
    )
    (net (code "66") (name "Net-(U11-E2)") (class "Default")
      (node (ref "R16") (pin "1") (pinfunction "1_1") (pintype "passive"))
      (node (ref "U11") (pin "6") (pinfunction "E2_6") (pintype "passive"))
    )
    (net (code "67") (name "Net-(U13-B1)") (class "Default")
      (node (ref "C17") (pin "2") (pinfunction "2_2") (pintype "passive"))
      (node (ref "R14") (pin "1") (pinfunction "1_1") (pintype "passive"))
      (node (ref "U13") (pin "2") (pinfunction "B1_2") (pintype "passive"))
      (node (ref "U13") (pin "7") (pinfunction "B2_7") (pintype "passive"))
      (node (ref "U13") (pin "8") (pinfunction "C2_8") (pintype "passive"))
    )
    (net (code "68") (name "Net-(U13-E1)") (class "Default")
      (node (ref "R17") (pin "2") (pinfunction "2_2") (pintype "passive"))
      (node (ref "U13") (pin "3") (pinfunction "E1_3") (pintype "passive"))
    )
    (net (code "69") (name "Net-(U13-E2)") (class "Default")
      (node (ref "R20") (pin "2") (pinfunction "2_2") (pintype "passive"))
      (node (ref "U13") (pin "6") (pinfunction "E2_6") (pintype "passive"))
    )
    (net (code "70") (name "VCC") (class "Default")
      (node (ref "C29") (pin "2") (pinfunction "2_2") (pintype "passive"))
      (node (ref "C30") (pin "1") (pinfunction "1_1") (pintype "passive"))
      (node (ref "U6") (pin "10") (pinfunction "+VAREG_10") (pintype "passive"))
      (node (ref "U6") (pin "24") (pinfunction "+VBD_24") (pintype "passive"))
      (node (ref "U6") (pin "34") (pinfunction "+VBD_34") (pintype "passive"))
      (node (ref "U6") (pin "37") (pinfunction "~{PD2}_37") (pintype "passive"))
    )
    (net (code "71") (name "unconnected-(U1-LOGIC_REF-Pad1)") (class "Default")
      (node (ref "U1") (pin "1") (pinfunction "LOGIC_REF_1") (pintype "passive"))
    )
    (net (code "72") (name "unconnected-(U1-{slash}DISABLE-Pad8)") (class "Default")
      (node (ref "U1") (pin "8") (pinfunction "/DISABLE_8") (pintype "passive"))
    )
    (net (code "73") (name "unconnected-(U4-LOGIC_REF-Pad1)") (class "Default")
      (node (ref "U4") (pin "1") (pinfunction "LOGIC_REF_1") (pintype "passive"))
    )
    (net (code "74") (name "unconnected-(U4-{slash}DISABLE-Pad8)") (class "Default")
      (node (ref "U4") (pin "8") (pinfunction "/DISABLE_8") (pintype "passive"))
    )
    (net (code "75") (name "unconnected-(U5-LOGIC_REF-Pad1)") (class "Default")
      (node (ref "U5") (pin "1") (pinfunction "LOGIC_REF_1") (pintype "passive"))
    )
    (net (code "76") (name "unconnected-(U5-{slash}DISABLE-Pad8)") (class "Default")
      (node (ref "U5") (pin "8") (pinfunction "/DISABLE_8") (pintype "passive"))
    )
    (net (code "77") (name "unconnected-(U6-NC-Pad11)") (class "Default")
      (node (ref "U6") (pin "11") (pinfunction "NC_11") (pintype "passive+no_connect"))
    )
    (net (code "78") (name "unconnected-(U6-REFOUT-Pad2)") (class "Default")
      (node (ref "U6") (pin "2") (pinfunction "REFOUT_2") (pintype "output+no_connect"))
    )
    (net (code "79") (name "unconnected-(U7-NC-Pad7)") (class "Default")
      (node (ref "U7") (pin "7") (pinfunction "NC_7") (pintype "passive"))
    )
    (net (code "80") (name "unconnected-(U11-NC-Pad4)") (class "Default")
      (node (ref "U11") (pin "4") (pinfunction "NC_4") (pintype "passive"))
    )
    (net (code "81") (name "unconnected-(U11-NC-Pad5)") (class "Default")
      (node (ref "U11") (pin "5") (pinfunction "NC_5") (pintype "passive"))
    )
    (net (code "82") (name "unconnected-(U13-NC-Pad4)") (class "Default")
      (node (ref "U13") (pin "4") (pinfunction "NC_4") (pintype "passive+no_connect"))
    )
    (net (code "83") (name "unconnected-(U13-NC-Pad5)") (class "Default")
      (node (ref "U13") (pin "5") (pinfunction "NC_5") (pintype "passive+no_connect"))
    )
  )
)
